# Sheet1.net
KiCad netlist of a schematic drawn in Altium Designer
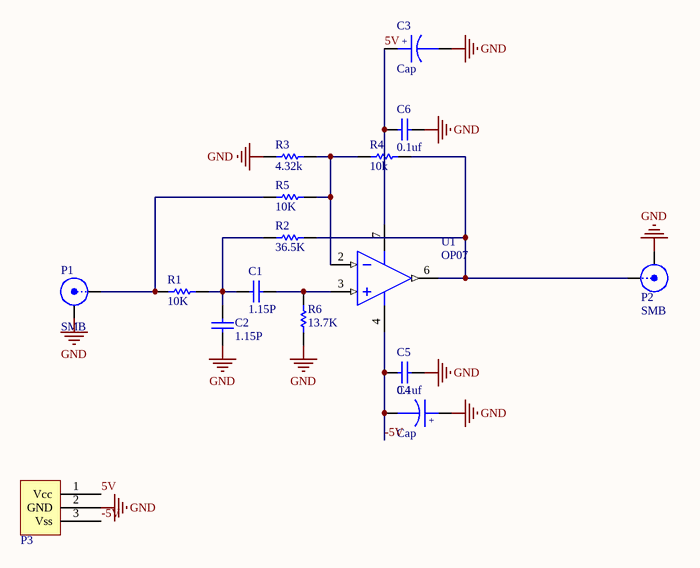
[diagram p0: Sheet1.SchDoc]

(export (version "E")
  (design (tool "Eeschema 10.0.6"))
  (components
    (comp (ref "C1") (value "1.15P") (footprint "0805") (libsource (lib "Schlib1") (part "Cap")))
    (comp (ref "C2") (value "1.15P") (footprint "0805") (libsource (lib "Schlib1") (part "Cap")))
    (comp (ref "C3")
      (value "Cap")
      (footprint "3216C-TYPE_A")
      (libsource (lib "Schlib1") (part "Tantalium Cap"))
    )
    (comp (ref "C4")
      (value "Cap")
      (footprint "3216C-TYPE_A")
      (libsource (lib "Schlib1") (part "Tantalium Cap"))
    )
    (comp (ref "C5") (value "0.1uf") (footprint "0805") (libsource (lib "Schlib1") (part "Cap")))
    (comp (ref "C6") (value "0.1uf") (footprint "0805") (libsource (lib "Schlib1") (part "Cap")))
    (comp (ref "P1")
      (value "SMB")
      (footprint "SMB_V-RJ45")
      (description "SMB Straight Connector")
      (fields (field (name "PUBLISHER") "Altium Limited"))
      (libsource (lib "Miscellaneous Connectors") (part "SMB"))
    )
    (comp (ref "P2")
      (value "SMB")
      (footprint "SMB_V-RJ45")
      (description "SMB Straight Connector")
      (fields (field (name "PUBLISHER") "Altium Limited"))
      (libsource (lib "Miscellaneous Connectors") (part "SMB"))
    )
    (comp (ref "P3")
      (value "XH2.54-3p")
      (footprint "XH2.54-3p")
      (libsource (lib "Schlib1") (part "XH2.54-3p"))
    )
    (comp (ref "R1") (value "10K") (footprint "0805") (libsource (lib "Schlib1") (part "Res")))
    (comp (ref "R2") (value "36.5K") (footprint "0805") (libsource (lib "Schlib1") (part "Res")))
    (comp (ref "R3") (value "4.32k") (footprint "0805") (libsource (lib "Schlib1") (part "Res")))
    (comp (ref "R4") (value "10k") (footprint "0805") (libsource (lib "Schlib1") (part "Res")))
    (comp (ref "R5") (value "10K") (footprint "0805") (libsource (lib "Schlib1") (part "Res")))
    (comp (ref "R6") (value "13.7K") (footprint "0805") (libsource (lib "Schlib1") (part "Res")))
    (comp (ref "U1") (value "OP07") (footprint "TI-JG8") (libsource (lib "Schlib1") (part "OP07")))
  )
  (nets
    (net (code "1") (name "/-5V") (class "Default")
      (node (ref "C4") (pin "2") (pinfunction "2_2") (pintype "passive"))
      (node (ref "C5") (pin "1") (pinfunction "1_1") (pintype "passive"))
      (node (ref "P3") (pin "3") (pinfunction "Vss_3") (pintype "passive"))
      (node (ref "U1") (pin "4") (pinfunction "V-_4") (pintype "power_in"))
    )
    (net (code "2") (name "/5V") (class "Default")
      (node (ref "C3") (pin "1") (pinfunction "1_1") (pintype "passive"))
      (node (ref "C6") (pin "1") (pinfunction "1_1") (pintype "passive"))
      (node (ref "P3") (pin "1") (pinfunction "Vcc_1") (pintype "passive"))
      (node (ref "U1") (pin "7") (pinfunction "V+_7") (pintype "power_in"))
    )
    (net (code "3") (name "GND") (class "Default")
      (node (ref "C2") (pin "1") (pinfunction "1_1") (pintype "passive"))
      (node (ref "C3") (pin "2") (pinfunction "2_2") (pintype "passive"))
      (node (ref "C4") (pin "1") (pinfunction "1_1") (pintype "passive"))
      (node (ref "C5") (pin "2") (pinfunction "2_2") (pintype "passive"))
      (node (ref "C6") (pin "2") (pinfunction "2_2") (pintype "passive"))
      (node (ref "P1") (pin "2") (pinfunction "Y_2") (pintype "passive"))
      (node (ref "P2") (pin "2") (pinfunction "Y_2") (pintype "passive"))
      (node (ref "P3") (pin "2") (pinfunction "GND_2") (pintype "passive"))
      (node (ref "R3") (pin "1") (pinfunction "1_1") (pintype "passive"))
      (node (ref "R6") (pin "1") (pinfunction "1_1") (pintype "passive"))
    )
    (net (code "4") (name "Net-(C1-Pad1)") (class "Default")
      (node (ref "C1") (pin "1") (pinfunction "1_1") (pintype "passive"))
      (node (ref "C2") (pin "2") (pinfunction "2_2") (pintype "passive"))
      (node (ref "R1") (pin "2") (pinfunction "2_2") (pintype "passive"))
      (node (ref "R2") (pin "1") (pinfunction "1_1") (pintype "passive"))
    )
    (net (code "5") (name "Net-(P1-X)") (class "Default")
      (node (ref "P1") (pin "1") (pinfunction "X_1") (pintype "passive"))
      (node (ref "R1") (pin "1") (pinfunction "1_1") (pintype "passive"))
      (node (ref "R5") (pin "1") (pinfunction "1_1") (pintype "passive"))
    )
    (net (code "6") (name "Net-(P2-X)") (class "Default")
      (node (ref "P2") (pin "1") (pinfunction "X_1") (pintype "passive"))
      (node (ref "R2") (pin "2") (pinfunction "2_2") (pintype "passive"))
      (node (ref "R4") (pin "2") (pinfunction "2_2") (pintype "passive"))
      (node (ref "U1") (pin "6") (pinfunction "OUT_6") (pintype "output"))
    )
    (net (code "7") (name "Net-(U1-IN+)") (class "Default")
      (node (ref "C1") (pin "2") (pinfunction "2_2") (pintype "passive"))
      (node (ref "R6") (pin "2") (pinfunction "2_2") (pintype "passive"))
      (node (ref "U1") (pin "3") (pinfunction "IN+_3") (pintype "input"))
    )
    (net (code "8") (name "Net-(U1-IN-)") (class "Default")
      (node (ref "R3") (pin "2") (pinfunction "2_2") (pintype "passive"))
      (node (ref "R4") (pin "1") (pinfunction "1_1") (pintype "passive"))
      (node (ref "R5") (pin "2") (pinfunction "2_2") (pintype "passive"))
      (node (ref "U1") (pin "2") (pinfunction "IN-_2") (pintype "input"))
    )
  )
)
